# USB.net
KiCad netlist of a schematic drawn in Altium Designer
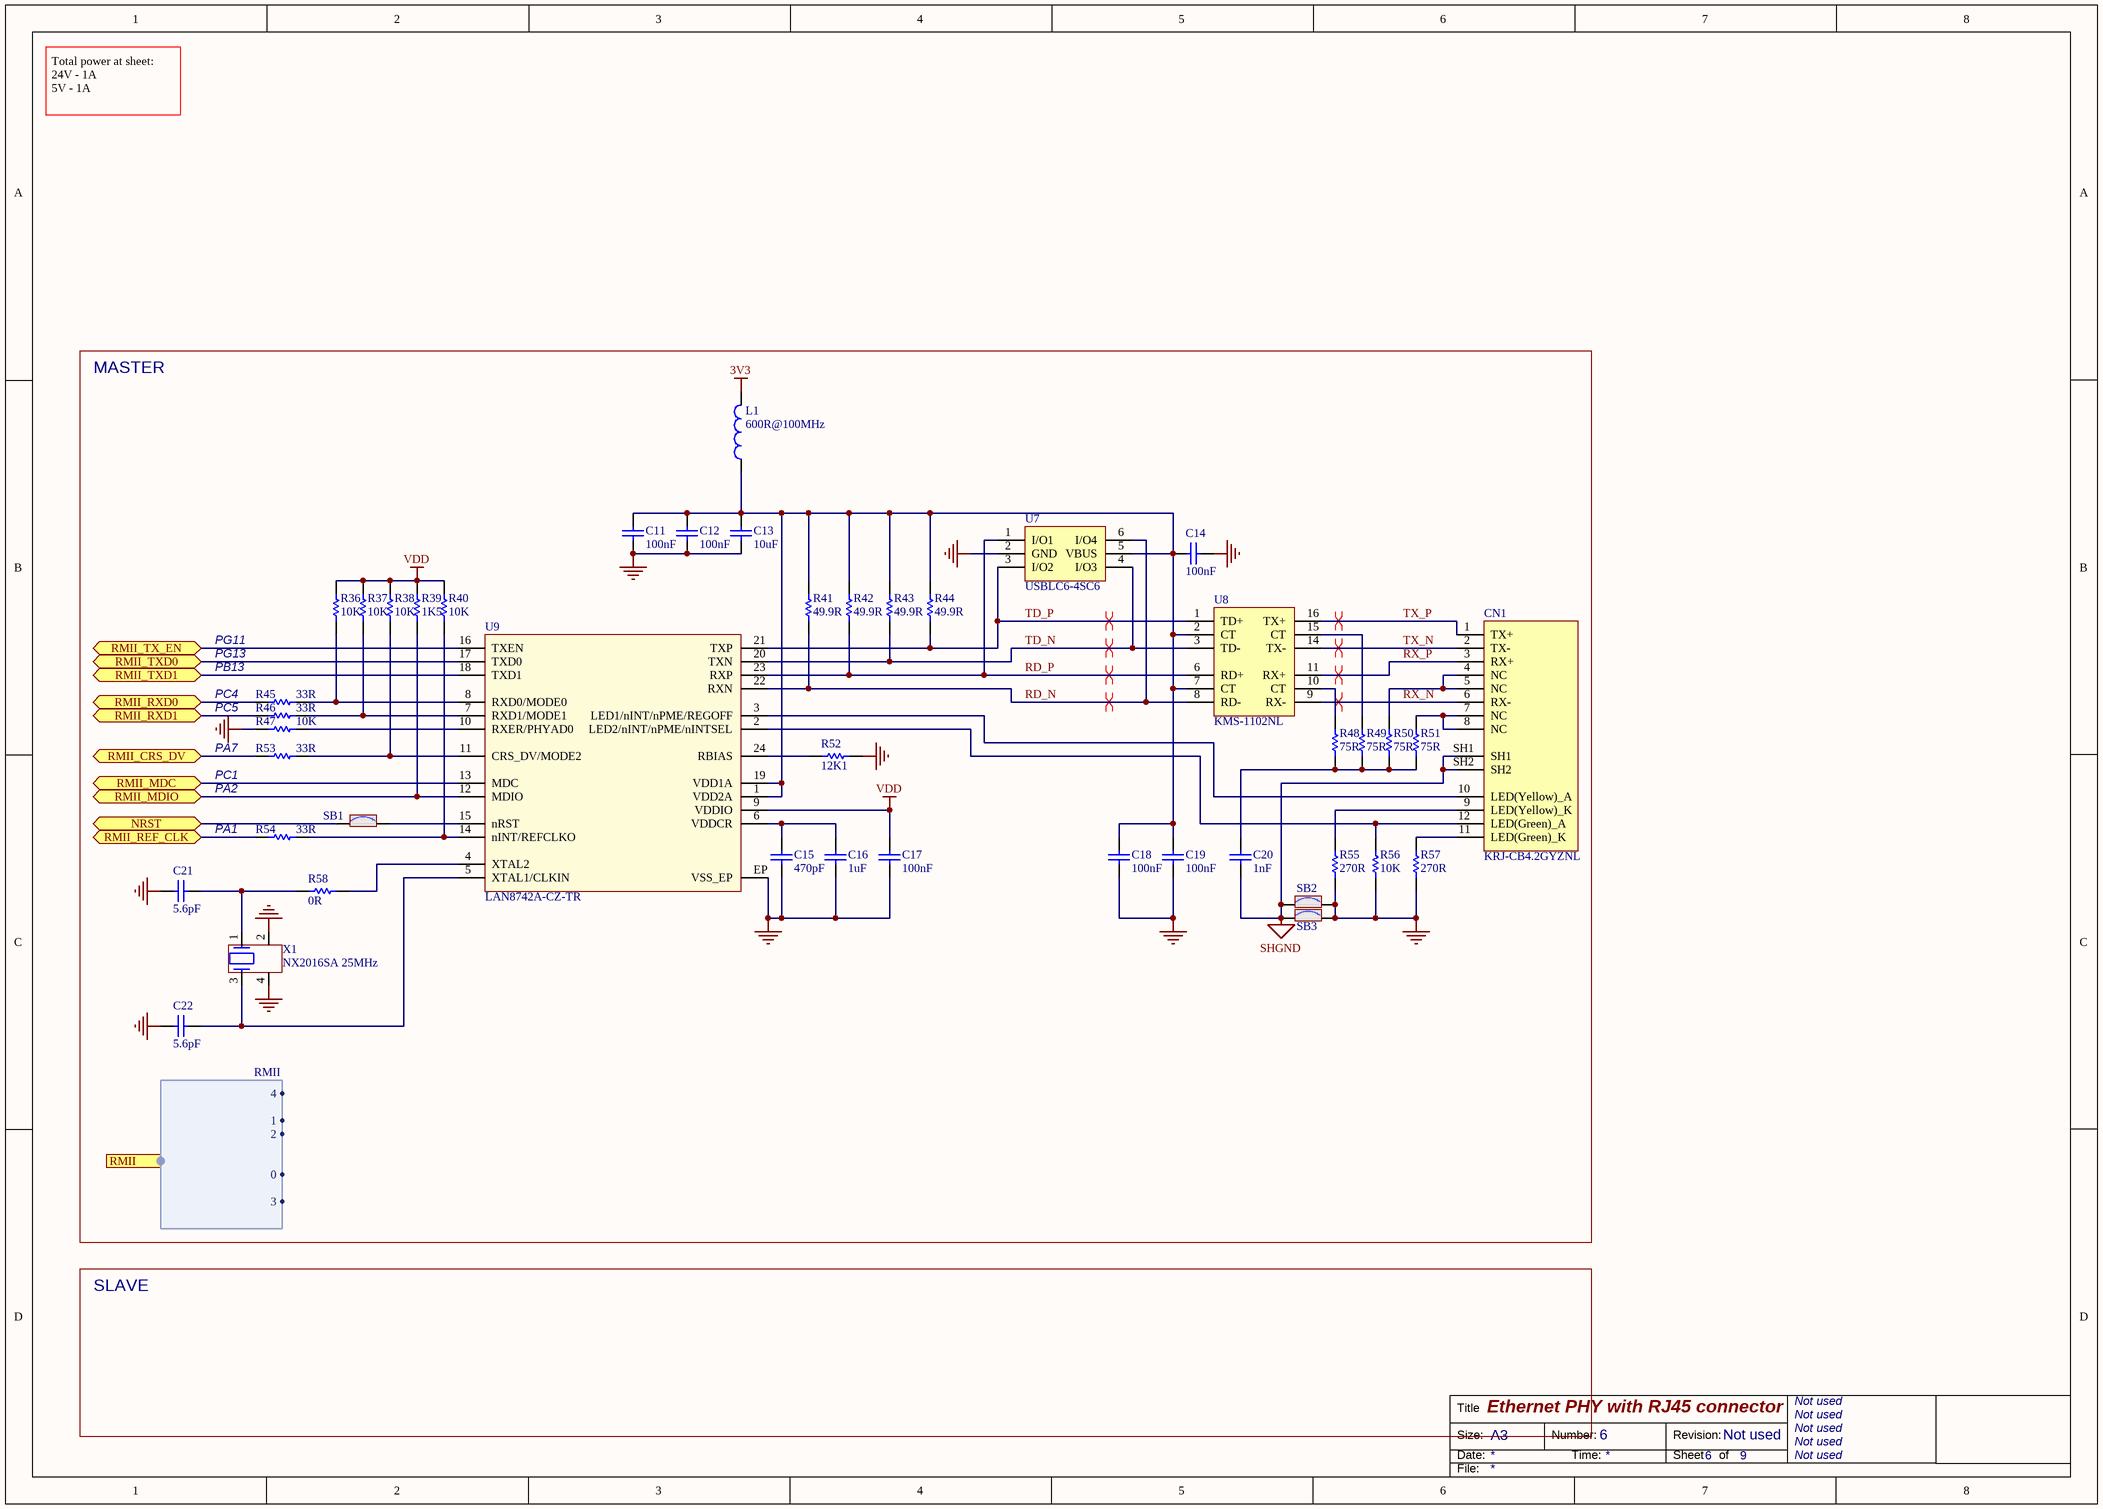
[diagram p0: USB.SchDoc]

(export (version "E")
  (design (tool "Eeschema 10.0.6"))
  (components
    (comp (ref "C11")
      (value "100nF")
      (footprint "C0603")
      (description "Capacitor, MLCC, 100nF, 6V3, X5R, 10%, 0603, T=0,8mm")
      (fields
        (field (name "INTERNAL_PART_NUMBER") "MCD-00237")
        (field (name "MANUFACTURER_PART_NUMBER") "CC0603KRX5R5BB104")
        (field (name "PROVIDED_BY") "SUBCO")
      )
      (libsource (lib "MCD_PARTS_database") (part "Capacitor"))
    )
    (comp (ref "C12")
      (value "100nF")
      (footprint "C0603")
      (description "Capacitor, MLCC, 100nF, 6V3, X5R, 10%, 0603, T=0,8mm")
      (fields
        (field (name "INTERNAL_PART_NUMBER") "MCD-00237")
        (field (name "MANUFACTURER_PART_NUMBER") "CC0603KRX5R5BB104")
        (field (name "PROVIDED_BY") "SUBCO")
      )
      (libsource (lib "MCD_PARTS_database") (part "Capacitor"))
    )
    (comp (ref "C13")
      (value "10uF")
      (footprint "C0603")
      (description "Capacitor, MLCC, 10µF, 10V, X5R, 10%, 0603, T=0.8mm")
      (fields
        (field (name "INTERNAL_PART_NUMBER") "MCD-01124")
        (field (name "MANUFACTURER_PART_NUMBER") "GRM188R61A106KAAL")
        (field (name "PROVIDED_BY") "SUBCO")
      )
      (libsource (lib "MCD_PARTS_database") (part "Capacitor"))
    )
    (comp (ref "C14")
      (value "100nF")
      (footprint "C0603")
      (description "Capacitor, MLCC, 100nF, 6V3, X5R, 10%, 0603, T=0,8mm")
      (fields
        (field (name "INTERNAL_PART_NUMBER") "MCD-00237")
        (field (name "MANUFACTURER_PART_NUMBER") "CC0603KRX5R5BB104")
        (field (name "PROVIDED_BY") "SUBCO")
      )
      (libsource (lib "MCD_PARTS_database") (part "Capacitor"))
    )
    (comp (ref "C15")
      (value "470pF")
      (footprint "C0402")
      (description "Capacitor, MLCC, 470pF, 50V, NPO, 5%, 0402, T=0,5mm")
      (fields
        (field (name "INTERNAL_PART_NUMBER") "MCD-00724")
        (field (name "MANUFACTURER_PART_NUMBER") "CC0402JRNPO9BN471")
        (field (name "PROVIDED_BY") "SUBCO")
      )
      (libsource (lib "MCD_PARTS_database") (part "Capacitor"))
    )
    (comp (ref "C16")
      (value "1uF")
      (footprint "C0402")
      (description "Capacitor, MLCC, 1uF, 6V3, X5R, 10%, 0402, T=0,5mm")
      (fields
        (field (name "INTERNAL_PART_NUMBER") "MCD-00095")
        (field (name "MANUFACTURER_PART_NUMBER") "GRM155R61E105KA12")
        (field (name "PROVIDED_BY") "SUBCO")
      )
      (libsource (lib "MCD_PARTS_database") (part "Capacitor"))
    )
    (comp (ref "C17")
      (value "100nF")
      (footprint "C0603")
      (description "Capacitor, MLCC, 100nF, 6V3, X5R, 10%, 0603, T=0,8mm")
      (fields
        (field (name "INTERNAL_PART_NUMBER") "MCD-00237")
        (field (name "MANUFACTURER_PART_NUMBER") "CC0603KRX5R5BB104")
        (field (name "PROVIDED_BY") "SUBCO")
      )
      (libsource (lib "MCD_PARTS_database") (part "Capacitor"))
    )
    (comp (ref "C18")
      (value "100nF")
      (footprint "C0603")
      (description "Capacitor, MLCC, 100nF, 6V3, X5R, 10%, 0603, T=0,8mm")
      (fields
        (field (name "INTERNAL_PART_NUMBER") "MCD-00237")
        (field (name "MANUFACTURER_PART_NUMBER") "CC0603KRX5R5BB104")
        (field (name "PROVIDED_BY") "SUBCO")
      )
      (libsource (lib "MCD_PARTS_database") (part "Capacitor"))
    )
    (comp (ref "C19")
      (value "100nF")
      (footprint "C0603")
      (description "Capacitor, MLCC, 100nF, 6V3, X5R, 10%, 0603, T=0,8mm")
      (fields
        (field (name "INTERNAL_PART_NUMBER") "MCD-00237")
        (field (name "MANUFACTURER_PART_NUMBER") "CC0603KRX5R5BB104")
        (field (name "PROVIDED_BY") "SUBCO")
      )
      (libsource (lib "MCD_PARTS_database") (part "Capacitor"))
    )
    (comp (ref "C20")
      (value "1nF")
      (footprint "C1206_H1P6")
      (description "Capacitor, MLCC, 1nF, 2KV, X7R, 10%, 1206, T=1,25mm")
      (fields
        (field (name "INTERNAL_PART_NUMBER") "MCD-00722")
        (field (name "MANUFACTURER_PART_NUMBER") "CC1206KKX7RDBB102")
        (field (name "PROVIDED_BY") "SUBCO")
      )
      (libsource (lib "MCD_PARTS_database") (part "Capacitor"))
    )
    (comp (ref "C21")
      (value "5.6pF")
      (footprint "C0402")
      (description "Capacitor, MLCC, 5.6pF, 50V, NPO, 5%, 0402, T=0,5mm")
      (fields
        (field (name "INTERNAL_PART_NUMBER") "MCD-01374")
        (field (name "MANUFACTURER_PART_NUMBER") "CC0402BRNPO9BN5R6")
        (field (name "PROVIDED_BY") "SUBCO")
      )
      (libsource (lib "MCD_PARTS_database") (part "Capacitor"))
    )
    (comp (ref "C22")
      (value "5.6pF")
      (footprint "C0402")
      (description "Capacitor, MLCC, 5.6pF, 50V, NPO, 5%, 0402, T=0,5mm")
      (fields
        (field (name "INTERNAL_PART_NUMBER") "MCD-01374")
        (field (name "MANUFACTURER_PART_NUMBER") "CC0402BRNPO9BN5R6")
        (field (name "PROVIDED_BY") "SUBCO")
      )
      (libsource (lib "MCD_PARTS_database") (part "Capacitor"))
    )
    (comp (ref "CN1")
      (value "KRJ-CB4.2GYZNL")
      (footprint "CON_RJ45_DGKYD_KRJ-CB4.2GYZNL")
      (description "RJ45 jack, single port, with LEDS, Metal shielded dip low profile")
      (fields
        (field (name "INTERNAL_PART_NUMBER") "MCD-00717")
        (field (name "MANUFACTURER") "DONGGUAN KEYOUDA ELECTRONIC TECHNOLOGY")
        (field (name "PROVIDED_BY") "SUBCO")
      )
      (libsource (lib "MCD_PARTS_database") (part "RJ45_KRJ-CB4.2GYZNL"))
    )
    (comp (ref "L1")
      (value "600R@100MHz")
      (footprint "L0603")
      (description "SMD Chip ferrite bead, 600R@100MHz +/-25%, 350mA, 500mohm DC, 0603, T=0.8mm")
      (fields
        (field (name "INTERNAL_PART_NUMBER") "MCD-00047")
        (field (name "MANUFACTURER_PART_NUMBER") "FCM1608KF-601T03")
        (field (name "PROVIDED_BY") "SUBCO")
      )
      (libsource (lib "MCD_PARTS_database") (part "BEAD"))
    )
    (comp (ref "R36")
      (value "10K")
      (footprint "R0402")
      (description "Resistor,10K,0402,1%,1/16W")
      (fields
        (field (name "INTERNAL_PART_NUMBER") "MCD-00053")
        (field (name "MANUFACTURER_PART_NUMBER") "RC0402FR-0710KL")
        (field (name "PROVIDED_BY") "SUBCO")
      )
      (libsource (lib "MCD_PARTS_database") (part "Resistor"))
    )
    (comp (ref "R37")
      (value "10K")
      (footprint "R0402")
      (description "Resistor,10K,0402,1%,1/16W")
      (fields
        (field (name "INTERNAL_PART_NUMBER") "MCD-00053")
        (field (name "MANUFACTURER_PART_NUMBER") "RC0402FR-0710KL")
        (field (name "PROVIDED_BY") "SUBCO")
      )
      (libsource (lib "MCD_PARTS_database") (part "Resistor"))
    )
    (comp (ref "R38")
      (value "10K")
      (footprint "R0402")
      (description "Resistor,10K,0402,1%,1/16W")
      (fields
        (field (name "INTERNAL_PART_NUMBER") "MCD-00053")
        (field (name "MANUFACTURER_PART_NUMBER") "RC0402FR-0710KL")
        (field (name "PROVIDED_BY") "SUBCO")
      )
      (libsource (lib "MCD_PARTS_database") (part "Resistor"))
    )
    (comp (ref "R39")
      (value "1K5")
      (footprint "R0402")
      (description "Resistor,1K5,0402,1%,1/16W")
      (fields
        (field (name "INTERNAL_PART_NUMBER") "MCD-00068")
        (field (name "MANUFACTURER_PART_NUMBER") "RC0402FR-071K5L")
        (field (name "PROVIDED_BY") "SUBCO")
      )
      (libsource (lib "MCD_PARTS_database") (part "Resistor"))
    )
    (comp (ref "R40")
      (value "10K")
      (footprint "R0402")
      (description "Resistor,10K,0402,1%,1/16W")
      (fields
        (field (name "INTERNAL_PART_NUMBER") "MCD-00053")
        (field (name "MANUFACTURER_PART_NUMBER") "RC0402FR-0710KL")
        (field (name "PROVIDED_BY") "SUBCO")
      )
      (libsource (lib "MCD_PARTS_database") (part "Resistor"))
    )
    (comp (ref "R41")
      (value "49.9R")
      (footprint "R0402")
      (description "Resistor,49R9,0402,1%,1/16W")
      (fields
        (field (name "INTERNAL_PART_NUMBER") "MCD-00565")
        (field (name "MANUFACTURER_PART_NUMBER") "RC0402FR-0749R9L")
        (field (name "PROVIDED_BY") "SUBCO")
      )
      (libsource (lib "MCD_PARTS_database") (part "Resistor"))
    )
    (comp (ref "R42")
      (value "49.9R")
      (footprint "R0402")
      (description "Resistor,49R9,0402,1%,1/16W")
      (fields
        (field (name "INTERNAL_PART_NUMBER") "MCD-00565")
        (field (name "MANUFACTURER_PART_NUMBER") "RC0402FR-0749R9L")
        (field (name "PROVIDED_BY") "SUBCO")
      )
      (libsource (lib "MCD_PARTS_database") (part "Resistor"))
    )
    (comp (ref "R43")
      (value "49.9R")
      (footprint "R0402")
      (description "Resistor,49R9,0402,1%,1/16W")
      (fields
        (field (name "INTERNAL_PART_NUMBER") "MCD-00565")
        (field (name "MANUFACTURER_PART_NUMBER") "RC0402FR-0749R9L")
        (field (name "PROVIDED_BY") "SUBCO")
      )
      (libsource (lib "MCD_PARTS_database") (part "Resistor"))
    )
    (comp (ref "R44")
      (value "49.9R")
      (footprint "R0402")
      (description "Resistor,49R9,0402,1%,1/16W")
      (fields
        (field (name "INTERNAL_PART_NUMBER") "MCD-00565")
        (field (name "MANUFACTURER_PART_NUMBER") "RC0402FR-0749R9L")
        (field (name "PROVIDED_BY") "SUBCO")
      )
      (libsource (lib "MCD_PARTS_database") (part "Resistor"))
    )
    (comp (ref "R45")
      (value "33R")
      (footprint "R0402")
      (description "Resistor,33R,0402,1%,1/16W")
      (fields
        (field (name "INTERNAL_PART_NUMBER") "MCD-00455")
        (field (name "MANUFACTURER_PART_NUMBER") "RC0402FR-0733RL")
        (field (name "PROVIDED_BY") "SUBCO")
      )
      (libsource (lib "MCD_PARTS_database") (part "Resistor"))
    )
    (comp (ref "R46")
      (value "33R")
      (footprint "R0402")
      (description "Resistor,33R,0402,1%,1/16W")
      (fields
        (field (name "INTERNAL_PART_NUMBER") "MCD-00455")
        (field (name "MANUFACTURER_PART_NUMBER") "RC0402FR-0733RL")
        (field (name "PROVIDED_BY") "SUBCO")
      )
      (libsource (lib "MCD_PARTS_database") (part "Resistor"))
    )
    (comp (ref "R47")
      (value "10K")
      (footprint "R0402")
      (description "Resistor,10K,0402,1%,1/16W")
      (fields
        (field (name "INTERNAL_PART_NUMBER") "MCD-00053")
        (field (name "MANUFACTURER_PART_NUMBER") "RC0402FR-0710KL")
        (field (name "PROVIDED_BY") "SUBCO")
      )
      (libsource (lib "MCD_PARTS_database") (part "Resistor"))
    )
    (comp (ref "R48")
      (value "75R")
      (footprint "R0402")
      (description "Resistor,75R,0402,1%,1/16W")
      (fields
        (field (name "INTERNAL_PART_NUMBER") "MCD-00515")
        (field (name "MANUFACTURER_PART_NUMBER") "RC0402FR-0775RL")
        (field (name "PROVIDED_BY") "SUBCO")
      )
      (libsource (lib "MCD_PARTS_database") (part "Resistor"))
    )
    (comp (ref "R49")
      (value "75R")
      (footprint "R0402")
      (description "Resistor,75R,0402,1%,1/16W")
      (fields
        (field (name "INTERNAL_PART_NUMBER") "MCD-00515")
        (field (name "MANUFACTURER_PART_NUMBER") "RC0402FR-0775RL")
        (field (name "PROVIDED_BY") "SUBCO")
      )
      (libsource (lib "MCD_PARTS_database") (part "Resistor"))
    )
    (comp (ref "R50")
      (value "75R")
      (footprint "R0402")
      (description "Resistor,75R,0402,1%,1/16W")
      (fields
        (field (name "INTERNAL_PART_NUMBER") "MCD-00515")
        (field (name "MANUFACTURER_PART_NUMBER") "RC0402FR-0775RL")
        (field (name "PROVIDED_BY") "SUBCO")
      )
      (libsource (lib "MCD_PARTS_database") (part "Resistor"))
    )
    (comp (ref "R51")
      (value "75R")
      (footprint "R0402")
      (description "Resistor,75R,0402,1%,1/16W")
      (fields
        (field (name "INTERNAL_PART_NUMBER") "MCD-00515")
        (field (name "MANUFACTURER_PART_NUMBER") "RC0402FR-0775RL")
        (field (name "PROVIDED_BY") "SUBCO")
      )
      (libsource (lib "MCD_PARTS_database") (part "Resistor"))
    )
    (comp (ref "R52")
      (value "12K1")
      (footprint "R0402")
      (description "Resistor,12K1,0402,1%,1/16W")
      (fields
        (field (name "INTERNAL_PART_NUMBER") "MCD-00723")
        (field (name "MANUFACTURER_PART_NUMBER") "RC0402FR-0712K1L")
        (field (name "PROVIDED_BY") "SUBCO")
      )
      (libsource (lib "MCD_PARTS_database") (part "Resistor"))
    )
    (comp (ref "R53")
      (value "33R")
      (footprint "R0402")
      (description "Resistor,33R,0402,1%,1/16W")
      (fields
        (field (name "INTERNAL_PART_NUMBER") "MCD-00455")
        (field (name "MANUFACTURER_PART_NUMBER") "RC0402FR-0733RL")
        (field (name "PROVIDED_BY") "SUBCO")
      )
      (libsource (lib "MCD_PARTS_database") (part "Resistor"))
    )
    (comp (ref "R54")
      (value "33R")
      (footprint "R0402")
      (description "Resistor,33R,0402,1%,1/16W")
      (fields
        (field (name "INTERNAL_PART_NUMBER") "MCD-00455")
        (field (name "MANUFACTURER_PART_NUMBER") "RC0402FR-0733RL")
        (field (name "PROVIDED_BY") "SUBCO")
      )
      (libsource (lib "MCD_PARTS_database") (part "Resistor"))
    )
    (comp (ref "R55")
      (value "270R")
      (footprint "R0402")
      (description "Resistor,270R,0402,1%,1/16W")
      (fields
        (field (name "INTERNAL_PART_NUMBER") "MCD-00441")
        (field (name "MANUFACTURER_PART_NUMBER") "RC0402FR-07270RL")
        (field (name "PROVIDED_BY") "SUBCO")
      )
      (libsource (lib "MCD_PARTS_database") (part "Resistor"))
    )
    (comp (ref "R56")
      (value "10K")
      (footprint "R0402")
      (description "Resistor,10K,0402,1%,1/16W")
      (fields
        (field (name "INTERNAL_PART_NUMBER") "MCD-00053")
        (field (name "MANUFACTURER_PART_NUMBER") "RC0402FR-0710KL")
        (field (name "PROVIDED_BY") "SUBCO")
      )
      (libsource (lib "MCD_PARTS_database") (part "Resistor"))
    )
    (comp (ref "R57")
      (value "270R")
      (footprint "R0402")
      (description "Resistor,270R,0402,1%,1/16W")
      (fields
        (field (name "INTERNAL_PART_NUMBER") "MCD-00441")
        (field (name "MANUFACTURER_PART_NUMBER") "RC0402FR-07270RL")
        (field (name "PROVIDED_BY") "SUBCO")
      )
      (libsource (lib "MCD_PARTS_database") (part "Resistor"))
    )
    (comp (ref "R58")
      (value "0R")
      (footprint "R0402")
      (description "Resistor,0R,0402,5%,1/16W")
      (fields
        (field (name "INTERNAL_PART_NUMBER") "MCD-00052")
        (field (name "MANUFACTURER_PART_NUMBER") "RC0402JR-070RL")
        (field (name "PROVIDED_BY") "SUBCO")
      )
      (libsource (lib "MCD_PARTS_database") (part "Resistor"))
    )
    (comp (ref "SB1")
      (value "SB_ON")
      (footprint "SOLDER-BRIDGE_R0603-0R")
      (description "Solder Bridge ON")
      (fields
        (field (name "INTERNAL_PART_NUMBER") "MCD-00071")
        (field (name "MANUFACTURER_PART_NUMBER") "RC0603JR-070RL")
        (field (name "PROVIDED_BY") "SUBCO")
      )
      (libsource (lib "MCD_PARTS_database") (part "SB_ON"))
    )
    (comp (ref "SB2")
      (value "SB_ON")
      (footprint "SOLDER-BRIDGE_R0603-0R")
      (description "Solder Bridge ON")
      (fields
        (field (name "INTERNAL_PART_NUMBER") "MCD-00071")
        (field (name "MANUFACTURER_PART_NUMBER") "RC0603JR-070RL")
        (field (name "PROVIDED_BY") "SUBCO")
      )
      (libsource (lib "MCD_PARTS_database") (part "SB_ON"))
    )
    (comp (ref "SB3")
      (value "SB_ON")
      (footprint "SOLDER-BRIDGE_R0603-0R")
      (description "Solder Bridge ON")
      (fields
        (field (name "INTERNAL_PART_NUMBER") "MCD-00071")
        (field (name "MANUFACTURER_PART_NUMBER") "RC0603JR-070RL")
        (field (name "PROVIDED_BY") "SUBCO")
      )
      (libsource (lib "MCD_PARTS_database") (part "SB_ON"))
    )
    (comp (ref "U7")
      (value "USBLC6-4SC6")
      (footprint "ESD_SOT23-6L")
      (description "Very low capacitance ESD protection , 4 lines")
      (fields
        (field (name "INTERNAL_PART_NUMBER") "MCD-00250")
        (field (name "MANUFACTURER") "STMICROELECTRONICS")
        (field (name "PROVIDED_BY") "SUBCO with ST control")
      )
      (libsource (lib "MCD_PARTS_database") (part "USBLC6-4SC6"))
    )
    (comp (ref "U8")
      (value "KMS-1102NL")
      (footprint "TRS_DGKYD_KMS-1102NL")
      (description "Discrete Magnetic Transformer Module, 16 pins, SMT, 100 Base-TX")
      (fields
        (field (name "INTERNAL_PART_NUMBER") "MCD-00718")
        (field (name "MANUFACTURER") "DONGGUAN KEYOUDA ELECTRONIC TECHNOLOGY")
        (field (name "PROVIDED_BY") "SUBCO")
      )
      (libsource (lib "MCD_PARTS_database") (part "KMS-1102NL"))
    )
    (comp (ref "U9")
      (value "LAN8742A-CZ-TR")
      (footprint "ICC_VQFN24-EPAD_4X4_P050")
      (description "10/100M RMII Ethernet transceiver")
      (fields
        (field (name "INTERNAL_PART_NUMBER") "MCD-00719")
        (field (name "MANUFACTURER") "MICROCHIP")
        (field (name "PROVIDED_BY") "SUBCO")
      )
      (libsource (lib "MCD_PARTS_database") (part "LAN8742A-CZ-TR"))
    )
    (comp (ref "X1")
      (value "NX2016SA 25MHz")
      (footprint "CRY_NX2016SA_4P")
      (description "Crystal 25MHz, 6pF, +-20ppm, 80ohms max, SMD")
      (fields
        (field (name "INTERNAL_PART_NUMBER") "MCD-01364")
        (field (name "MANUFACTURER_PART_NUMBER") "NX2016SA 25MHz EXS00A-CS11321")
        (field (name "PROVIDED_BY") "SUBCO")
      )
      (libsource (lib "MCD_PARTS_database") (part "XTAL_4_PINS"))
    )
  )
  (nets
    (net (code "2") (name "/NRST") (class "Default")
      (node (ref "SB1") (pin "1") (pinfunction "1_1") (pintype "passive"))
    )
    (net (code "3") (name "/RD_N") (class "Default")
      (node (ref "R41") (pin "1") (pinfunction "1_1") (pintype "passive"))
      (node (ref "U7") (pin "6") (pinfunction "I/O4_6") (pintype "passive"))
      (node (ref "U8") (pin "8") (pinfunction "RD-_8") (pintype "passive"))
      (node (ref "U9") (pin "22") (pinfunction "RXN_22") (pintype "passive"))
    )
    (net (code "4") (name "/RD_P") (class "Default")
      (node (ref "R42") (pin "1") (pinfunction "1_1") (pintype "passive"))
      (node (ref "U7") (pin "1") (pinfunction "I/O1_1") (pintype "passive"))
      (node (ref "U8") (pin "6") (pinfunction "RD+_6") (pintype "passive"))
      (node (ref "U9") (pin "23") (pinfunction "RXP_23") (pintype "passive"))
    )
    (net (code "5") (name "/RMII_CRS_DV") (class "Default")
      (node (ref "R53") (pin "1") (pinfunction "1_1") (pintype "passive"))
    )
    (net (code "6") (name "/RMII_MDC") (class "Default")
      (node (ref "U9") (pin "13") (pinfunction "MDC_13") (pintype "passive"))
    )
    (net (code "7") (name "/RMII_MDIO") (class "Default")
      (node (ref "R39") (pin "1") (pinfunction "1_1") (pintype "passive"))
      (node (ref "U9") (pin "12") (pinfunction "MDIO_12") (pintype "passive"))
    )
    (net (code "8") (name "/RMII_REF_CLK") (class "Default")
      (node (ref "R54") (pin "1") (pinfunction "1_1") (pintype "passive"))
    )
    (net (code "9") (name "/RMII_RXD0") (class "Default")
      (node (ref "R45") (pin "1") (pinfunction "1_1") (pintype "passive"))
    )
    (net (code "10") (name "/RMII_RXD1") (class "Default")
      (node (ref "R46") (pin "1") (pinfunction "1_1") (pintype "passive"))
    )
    (net (code "11") (name "/RMII_TXD0") (class "Default")
      (node (ref "U9") (pin "17") (pinfunction "TXD0_17") (pintype "passive"))
    )
    (net (code "12") (name "/RMII_TXD1") (class "Default")
      (node (ref "U9") (pin "18") (pinfunction "TXD1_18") (pintype "passive"))
    )
    (net (code "13") (name "/RMII_TX_EN") (class "Default")
      (node (ref "U9") (pin "16") (pinfunction "TXEN_16") (pintype "passive"))
    )
    (net (code "14") (name "/RX_N") (class "Default")
      (node (ref "CN1") (pin "6") (pinfunction "RX-_6") (pintype "passive"))
      (node (ref "U8") (pin "9") (pinfunction "RX-_9") (pintype "passive"))
    )
    (net (code "15") (name "/RX_P") (class "Default")
      (node (ref "CN1") (pin "3") (pinfunction "RX+_3") (pintype "passive"))
      (node (ref "U8") (pin "11") (pinfunction "RX+_11") (pintype "passive"))
    )
    (net (code "16") (name "/TD_N") (class "Default")
      (node (ref "R43") (pin "1") (pinfunction "1_1") (pintype "passive"))
      (node (ref "U7") (pin "4") (pinfunction "I/O3_4") (pintype "passive"))
      (node (ref "U8") (pin "3") (pinfunction "TD-_3") (pintype "passive"))
      (node (ref "U9") (pin "20") (pinfunction "TXN_20") (pintype "passive"))
    )
    (net (code "17") (name "/TD_P") (class "Default")
      (node (ref "R44") (pin "1") (pinfunction "1_1") (pintype "passive"))
      (node (ref "U7") (pin "3") (pinfunction "I/O2_3") (pintype "passive"))
      (node (ref "U8") (pin "1") (pinfunction "TD+_1") (pintype "passive"))
      (node (ref "U9") (pin "21") (pinfunction "TXP_21") (pintype "passive"))
    )
    (net (code "18") (name "/TX_N") (class "Default")
      (node (ref "CN1") (pin "2") (pinfunction "TX-_2") (pintype "passive"))
      (node (ref "U8") (pin "14") (pinfunction "TX-_14") (pintype "passive"))
    )
    (net (code "19") (name "/TX_P") (class "Default")
      (node (ref "CN1") (pin "1") (pinfunction "TX+_1") (pintype "passive"))
      (node (ref "U8") (pin "16") (pinfunction "TX+_16") (pintype "passive"))
    )
    (net (code "21") (name "3V3") (class "Default")
      (node (ref "L1") (pin "2") (pinfunction "2_2") (pintype "passive"))
    )
    (net (code "22") (name "GND") (class "Default")
      (node (ref "C11") (pin "1") (pinfunction "1_1") (pintype "passive"))
      (node (ref "C12") (pin "1") (pinfunction "1_1") (pintype "passive"))
      (node (ref "C13") (pin "1") (pinfunction "1_1") (pintype "passive"))
      (node (ref "C14") (pin "2") (pinfunction "2_2") (pintype "passive"))
      (node (ref "C15") (pin "1") (pinfunction "1_1") (pintype "passive"))
      (node (ref "C16") (pin "1") (pinfunction "1_1") (pintype "passive"))
      (node (ref "C17") (pin "1") (pinfunction "1_1") (pintype "passive"))
      (node (ref "C18") (pin "1") (pinfunction "1_1") (pintype "passive"))
      (node (ref "C19") (pin "1") (pinfunction "1_1") (pintype "passive"))
      (node (ref "C21") (pin "1") (pinfunction "1_1") (pintype "passive"))
      (node (ref "C22") (pin "1") (pinfunction "1_1") (pintype "passive"))
      (node (ref "R47") (pin "2") (pinfunction "2_2") (pintype "passive"))
      (node (ref "R52") (pin "2") (pinfunction "2_2") (pintype "passive"))
      (node (ref "R55") (pin "1") (pinfunction "1_1") (pintype "passive"))
      (node (ref "R56") (pin "1") (pinfunction "1_1") (pintype "passive"))
      (node (ref "R57") (pin "1") (pinfunction "1_1") (pintype "passive"))
      (node (ref "SB2") (pin "2") (pinfunction "2_2") (pintype "passive"))
      (node (ref "SB3") (pin "2") (pinfunction "2_2") (pintype "passive"))
      (node (ref "U7") (pin "2") (pinfunction "GND_2") (pintype "passive"))
      (node (ref "U9") (pin "EP") (pinfunction "VSS_EP_EP") (pintype "passive"))
      (node (ref "X1") (pin "2") (pinfunction "2_2") (pintype "passive"))
      (node (ref "X1") (pin "4") (pinfunction "4_4") (pintype "passive"))
    )
    (net (code "23") (name "Net-(C20-Pad2)") (class "Default")
      (node (ref "C20") (pin "2") (pinfunction "2_2") (pintype "passive"))
      (node (ref "R48") (pin "1") (pinfunction "1_1") (pintype "passive"))
      (node (ref "R49") (pin "1") (pinfunction "1_1") (pintype "passive"))
      (node (ref "R50") (pin "1") (pinfunction "1_1") (pintype "passive"))
      (node (ref "R51") (pin "1") (pinfunction "1_1") (pintype "passive"))
    )
    (net (code "24") (name "Net-(C21-Pad2)") (class "Default")
      (node (ref "C21") (pin "2") (pinfunction "2_2") (pintype "passive"))
      (node (ref "R58") (pin "1") (pinfunction "1_1") (pintype "passive"))
      (node (ref "X1") (pin "1") (pinfunction "1_1") (pintype "passive"))
    )
    (net (code "25") (name "Net-(CN1-LED(Green)_A)") (class "Default")
      (node (ref "CN1") (pin "12") (pinfunction "LED(Green)_A_12") (pintype "passive"))
      (node (ref "R56") (pin "2") (pinfunction "2_2") (pintype "passive"))
      (node (ref "U9") (pin "2") (pinfunction "LED2/nINT/nPME/nINTSEL_2") (pintype "passive"))
    )
    (net (code "26") (name "Net-(CN1-LED(Green)_K)") (class "Default")
      (node (ref "CN1") (pin "11") (pinfunction "LED(Green)_K_11") (pintype "passive"))
      (node (ref "R57") (pin "2") (pinfunction "2_2") (pintype "passive"))
    )
    (net (code "27") (name "Net-(CN1-LED(Yellow)_A)") (class "Default")
      (node (ref "CN1") (pin "10") (pinfunction "LED(Yellow)_A_10") (pintype "passive"))
      (node (ref "U9") (pin "3") (pinfunction "LED1/nINT/nPME/REGOFF_3") (pintype "passive"))
    )
    (net (code "28") (name "Net-(CN1-LED(Yellow)_K)") (class "Default")
      (node (ref "CN1") (pin "9") (pinfunction "LED(Yellow)_K_9") (pintype "passive"))
      (node (ref "R55") (pin "2") (pinfunction "2_2") (pintype "passive"))
    )
    (net (code "29") (name "Net-(CN1-NC-Pad4)") (class "Default")
      (node (ref "CN1") (pin "4") (pinfunction "NC_4") (pintype "passive"))
      (node (ref "CN1") (pin "5") (pinfunction "NC_5") (pintype "passive"))
      (node (ref "R50") (pin "2") (pinfunction "2_2") (pintype "passive"))
    )
    (net (code "30") (name "Net-(CN1-NC-Pad7)") (class "Default")
      (node (ref "CN1") (pin "7") (pinfunction "NC_7") (pintype "passive"))
      (node (ref "CN1") (pin "8") (pinfunction "NC_8") (pintype "passive"))
      (node (ref "R51") (pin "2") (pinfunction "2_2") (pintype "passive"))
    )
    (net (code "31") (name "Net-(R48-Pad2)") (class "Default")
      (node (ref "R48") (pin "2") (pinfunction "2_2") (pintype "passive"))
      (node (ref "U8") (pin "10") (pinfunction "CT_10") (pintype "passive"))
    )
    (net (code "32") (name "Net-(R49-Pad2)") (class "Default")
      (node (ref "R49") (pin "2") (pinfunction "2_2") (pintype "passive"))
      (node (ref "U8") (pin "15") (pinfunction "CT_15") (pintype "passive"))
    )
    (net (code "33") (name "Net-(U7-VBUS)") (class "Default")
      (node (ref "C11") (pin "2") (pinfunction "2_2") (pintype "passive"))
      (node (ref "C12") (pin "2") (pinfunction "2_2") (pintype "passive"))
      (node (ref "C13") (pin "2") (pinfunction "2_2") (pintype "passive"))
      (node (ref "C14") (pin "1") (pinfunction "1_1") (pintype "passive"))
      (node (ref "C18") (pin "2") (pinfunction "2_2") (pintype "passive"))
      (node (ref "C19") (pin "2") (pinfunction "2_2") (pintype "passive"))
      (node (ref "L1") (pin "1") (pinfunction "1_1") (pintype "passive"))
      (node (ref "R41") (pin "2") (pinfunction "2_2") (pintype "passive"))
      (node (ref "R42") (pin "2") (pinfunction "2_2") (pintype "passive"))
      (node (ref "R43") (pin "2") (pinfunction "2_2") (pintype "passive"))
      (node (ref "R44") (pin "2") (pinfunction "2_2") (pintype "passive"))
      (node (ref "U7") (pin "5") (pinfunction "VBUS_5") (pintype "passive"))
      (node (ref "U8") (pin "2") (pinfunction "CT_2") (pintype "passive"))
      (node (ref "U8") (pin "7") (pinfunction "CT_7") (pintype "passive"))
      (node (ref "U9") (pin "1") (pinfunction "VDD2A_1") (pintype "passive"))
      (node (ref "U9") (pin "19") (pinfunction "VDD1A_19") (pintype "passive"))
    )
    (net (code "34") (name "Net-(U9-CRS_DV{slash}MODE2)") (class "Default")
      (node (ref "R38") (pin "1") (pinfunction "1_1") (pintype "passive"))
      (node (ref "R53") (pin "2") (pinfunction "2_2") (pintype "passive"))
      (node (ref "U9") (pin "11") (pinfunction "CRS_DV/MODE2_11") (pintype "passive"))
    )
    (net (code "35") (name "Net-(U9-RBIAS)") (class "Default")
      (node (ref "R52") (pin "1") (pinfunction "1_1") (pintype "passive"))
      (node (ref "U9") (pin "24") (pinfunction "RBIAS_24") (pintype "passive"))
    )
    (net (code "36") (name "Net-(U9-RXD0{slash}MODE0)") (class "Default")
      (node (ref "R36") (pin "1") (pinfunction "1_1") (pintype "passive"))
      (node (ref "R45") (pin "2") (pinfunction "2_2") (pintype "passive"))
      (node (ref "U9") (pin "8") (pinfunction "RXD0/MODE0_8") (pintype "passive"))
    )
    (net (code "37") (name "Net-(U9-RXD1{slash}MODE1)") (class "Default")
      (node (ref "R37") (pin "1") (pinfunction "1_1") (pintype "passive"))
      (node (ref "R46") (pin "2") (pinfunction "2_2") (pintype "passive"))
      (node (ref "U9") (pin "7") (pinfunction "RXD1/MODE1_7") (pintype "passive"))
    )
    (net (code "38") (name "Net-(U9-RXER{slash}PHYAD0)") (class "Default")
      (node (ref "R47") (pin "1") (pinfunction "1_1") (pintype "passive"))
      (node (ref "U9") (pin "10") (pinfunction "RXER/PHYAD0_10") (pintype "passive"))
    )
    (net (code "39") (name "Net-(U9-VDDCR)") (class "Default")
      (node (ref "C15") (pin "2") (pinfunction "2_2") (pintype "passive"))
      (node (ref "C16") (pin "2") (pinfunction "2_2") (pintype "passive"))
      (node (ref "U9") (pin "6") (pinfunction "VDDCR_6") (pintype "passive"))
    )
    (net (code "40") (name "Net-(U9-XTAL1{slash}CLKIN)") (class "Default")
      (node (ref "C22") (pin "2") (pinfunction "2_2") (pintype "passive"))
      (node (ref "U9") (pin "5") (pinfunction "XTAL1/CLKIN_5") (pintype "passive"))
      (node (ref "X1") (pin "3") (pinfunction "3_3") (pintype "passive"))
    )
    (net (code "41") (name "Net-(U9-XTAL2)") (class "Default")
      (node (ref "R58") (pin "2") (pinfunction "2_2") (pintype "passive"))
      (node (ref "U9") (pin "4") (pinfunction "XTAL2_4") (pintype "passive"))
    )
    (net (code "42") (name "Net-(U9-nINT{slash}REFCLKO)") (class "Default")
      (node (ref "R40") (pin "1") (pinfunction "1_1") (pintype "passive"))
      (node (ref "R54") (pin "2") (pinfunction "2_2") (pintype "passive"))
      (node (ref "U9") (pin "14") (pinfunction "nINT/REFCLKO_14") (pintype "passive"))
    )
    (net (code "43") (name "Net-(U9-nRST)") (class "Default")
      (node (ref "SB1") (pin "2") (pinfunction "2_2") (pintype "passive"))
      (node (ref "U9") (pin "15") (pinfunction "nRST_15") (pintype "passive"))
    )
    (net (code "44") (name "SHGND") (class "Default")
      (node (ref "C20") (pin "1") (pinfunction "1_1") (pintype "passive"))
      (node (ref "CN1") (pin "SH1") (pinfunction "SH1_SH1") (pintype "passive"))
      (node (ref "CN1") (pin "SH2") (pinfunction "SH2_SH2") (pintype "passive"))
      (node (ref "SB2") (pin "1") (pinfunction "1_1") (pintype "passive"))
      (node (ref "SB3") (pin "1") (pinfunction "1_1") (pintype "passive"))
    )
    (net (code "45") (name "VDD") (class "Default")
      (node (ref "C17") (pin "2") (pinfunction "2_2") (pintype "passive"))
      (node (ref "R36") (pin "2") (pinfunction "2_2") (pintype "passive"))
      (node (ref "R37") (pin "2") (pinfunction "2_2") (pintype "passive"))
      (node (ref "R38") (pin "2") (pinfunction "2_2") (pintype "passive"))
      (node (ref "R39") (pin "2") (pinfunction "2_2") (pintype "passive"))
      (node (ref "R40") (pin "2") (pinfunction "2_2") (pintype "passive"))
      (node (ref "U9") (pin "9") (pinfunction "VDDIO_9") (pintype "passive"))
    )
  )
)
